# W108C.net
KiCad netlist of a schematic drawn in EAGLE
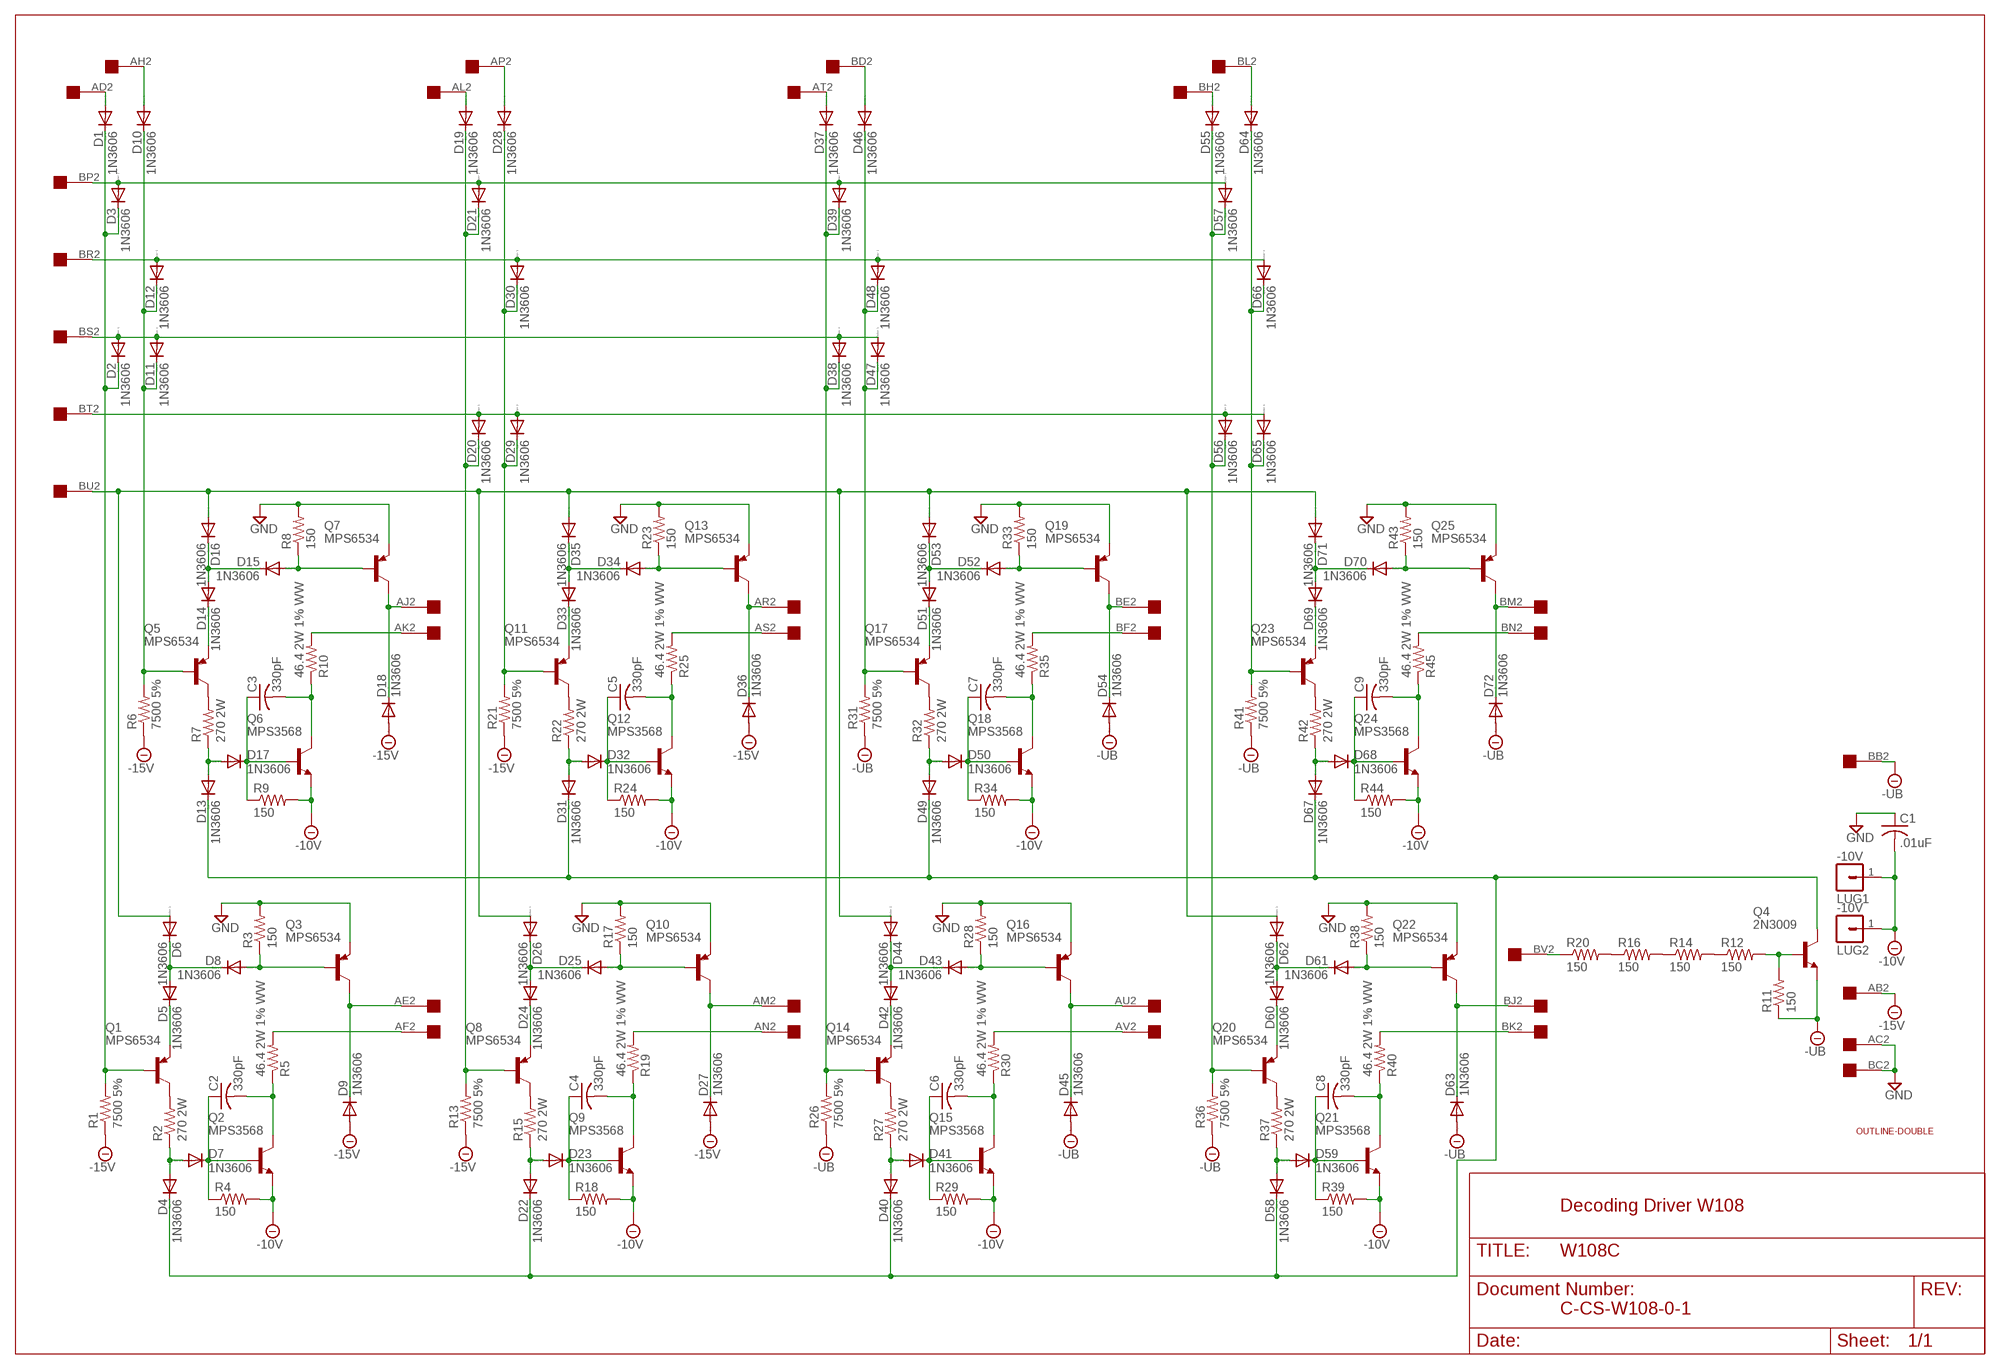
[diagram p0: schematic, sheet 1]

(export (version "E")
  (design (tool "Eeschema 10.0.6"))
  (components
    (comp (ref "C1")
      (value ".01uF")
      (footprint "eagle-import:C075-032X103")
      (libsource (lib "eagle-import") (part "C-US075-032X103"))
    )
    (comp (ref "C2")
      (value "330pF")
      (footprint "eagle-import:C075-032X103")
      (libsource (lib "eagle-import") (part "C-US075-032X103"))
    )
    (comp (ref "C3")
      (value "330pF")
      (footprint "eagle-import:C075-032X103")
      (libsource (lib "eagle-import") (part "C-US075-032X103"))
    )
    (comp (ref "C4")
      (value "330pF")
      (footprint "eagle-import:C075-032X103")
      (libsource (lib "eagle-import") (part "C-US075-032X103"))
    )
    (comp (ref "C5")
      (value "330pF")
      (footprint "eagle-import:C075-032X103")
      (libsource (lib "eagle-import") (part "C-US075-032X103"))
    )
    (comp (ref "C6")
      (value "330pF")
      (footprint "eagle-import:C075-032X103")
      (libsource (lib "eagle-import") (part "C-US075-032X103"))
    )
    (comp (ref "C7")
      (value "330pF")
      (footprint "eagle-import:C075-032X103")
      (libsource (lib "eagle-import") (part "C-US075-032X103"))
    )
    (comp (ref "C8")
      (value "330pF")
      (footprint "eagle-import:C075-032X103")
      (libsource (lib "eagle-import") (part "C-US075-032X103"))
    )
    (comp (ref "C9")
      (value "330pF")
      (footprint "eagle-import:C075-032X103")
      (libsource (lib "eagle-import") (part "C-US075-032X103"))
    )
    (comp (ref "D1")
      (value "1N3606")
      (footprint "eagle-import:DO35-10")
      (libsource (lib "eagle-import") (part "1N4148DO35-10"))
    )
    (comp (ref "D2")
      (value "1N3606")
      (footprint "eagle-import:DO35-10")
      (libsource (lib "eagle-import") (part "1N4148DO35-10"))
    )
    (comp (ref "D3")
      (value "1N3606")
      (footprint "eagle-import:DO35-10")
      (libsource (lib "eagle-import") (part "1N4148DO35-10"))
    )
    (comp (ref "D4")
      (value "1N3606")
      (footprint "eagle-import:DO35-10")
      (libsource (lib "eagle-import") (part "1N4148DO35-10"))
    )
    (comp (ref "D5")
      (value "1N3606")
      (footprint "eagle-import:DO35-10")
      (libsource (lib "eagle-import") (part "1N4148DO35-10"))
    )
    (comp (ref "D6")
      (value "1N3606")
      (footprint "eagle-import:DO35-10")
      (libsource (lib "eagle-import") (part "1N4148DO35-10"))
    )
    (comp (ref "D7")
      (value "1N3606")
      (footprint "eagle-import:DO35-10")
      (libsource (lib "eagle-import") (part "1N4148DO35-10"))
    )
    (comp (ref "D8")
      (value "1N3606")
      (footprint "eagle-import:DO35-10")
      (libsource (lib "eagle-import") (part "1N4148DO35-10"))
    )
    (comp (ref "D9")
      (value "1N3606")
      (footprint "eagle-import:DO35-10")
      (libsource (lib "eagle-import") (part "1N4148DO35-10"))
    )
    (comp (ref "D10")
      (value "1N3606")
      (footprint "eagle-import:DO35-10")
      (libsource (lib "eagle-import") (part "1N4148DO35-10"))
    )
    (comp (ref "D11")
      (value "1N3606")
      (footprint "eagle-import:DO35-10")
      (libsource (lib "eagle-import") (part "1N4148DO35-10"))
    )
    (comp (ref "D12")
      (value "1N3606")
      (footprint "eagle-import:DO35-10")
      (libsource (lib "eagle-import") (part "1N4148DO35-10"))
    )
    (comp (ref "D13")
      (value "1N3606")
      (footprint "eagle-import:DO35-10")
      (libsource (lib "eagle-import") (part "1N4148DO35-10"))
    )
    (comp (ref "D14")
      (value "1N3606")
      (footprint "eagle-import:DO35-10")
      (libsource (lib "eagle-import") (part "1N4148DO35-10"))
    )
    (comp (ref "D15")
      (value "1N3606")
      (footprint "eagle-import:DO35-10")
      (libsource (lib "eagle-import") (part "1N4148DO35-10"))
    )
    (comp (ref "D16")
      (value "1N3606")
      (footprint "eagle-import:DO35-10")
      (libsource (lib "eagle-import") (part "1N4148DO35-10"))
    )
    (comp (ref "D17")
      (value "1N3606")
      (footprint "eagle-import:DO35-10")
      (libsource (lib "eagle-import") (part "1N4148DO35-10"))
    )
    (comp (ref "D18")
      (value "1N3606")
      (footprint "eagle-import:DO35-10")
      (libsource (lib "eagle-import") (part "1N4148DO35-10"))
    )
    (comp (ref "D19")
      (value "1N3606")
      (footprint "eagle-import:DO35-10")
      (libsource (lib "eagle-import") (part "1N4148DO35-10"))
    )
    (comp (ref "D20")
      (value "1N3606")
      (footprint "eagle-import:DO35-10")
      (libsource (lib "eagle-import") (part "1N4148DO35-10"))
    )
    (comp (ref "D21")
      (value "1N3606")
      (footprint "eagle-import:DO35-10")
      (libsource (lib "eagle-import") (part "1N4148DO35-10"))
    )
    (comp (ref "D22")
      (value "1N3606")
      (footprint "eagle-import:DO35-10")
      (libsource (lib "eagle-import") (part "1N4148DO35-10"))
    )
    (comp (ref "D23")
      (value "1N3606")
      (footprint "eagle-import:DO35-10")
      (libsource (lib "eagle-import") (part "1N4148DO35-10"))
    )
    (comp (ref "D24")
      (value "1N3606")
      (footprint "eagle-import:DO35-10")
      (libsource (lib "eagle-import") (part "1N4148DO35-10"))
    )
    (comp (ref "D25")
      (value "1N3606")
      (footprint "eagle-import:DO35-10")
      (libsource (lib "eagle-import") (part "1N4148DO35-10"))
    )
    (comp (ref "D26")
      (value "1N3606")
      (footprint "eagle-import:DO35-10")
      (libsource (lib "eagle-import") (part "1N4148DO35-10"))
    )
    (comp (ref "D27")
      (value "1N3606")
      (footprint "eagle-import:DO35-10")
      (libsource (lib "eagle-import") (part "1N4148DO35-10"))
    )
    (comp (ref "D28")
      (value "1N3606")
      (footprint "eagle-import:DO35-10")
      (libsource (lib "eagle-import") (part "1N4148DO35-10"))
    )
    (comp (ref "D29")
      (value "1N3606")
      (footprint "eagle-import:DO35-10")
      (libsource (lib "eagle-import") (part "1N4148DO35-10"))
    )
    (comp (ref "D30")
      (value "1N3606")
      (footprint "eagle-import:DO35-10")
      (libsource (lib "eagle-import") (part "1N4148DO35-10"))
    )
    (comp (ref "D31")
      (value "1N3606")
      (footprint "eagle-import:DO35-10")
      (libsource (lib "eagle-import") (part "1N4148DO35-10"))
    )
    (comp (ref "D32")
      (value "1N3606")
      (footprint "eagle-import:DO35-10")
      (libsource (lib "eagle-import") (part "1N4148DO35-10"))
    )
    (comp (ref "D33")
      (value "1N3606")
      (footprint "eagle-import:DO35-10")
      (libsource (lib "eagle-import") (part "1N4148DO35-10"))
    )
    (comp (ref "D34")
      (value "1N3606")
      (footprint "eagle-import:DO35-10")
      (libsource (lib "eagle-import") (part "1N4148DO35-10"))
    )
    (comp (ref "D35")
      (value "1N3606")
      (footprint "eagle-import:DO35-10")
      (libsource (lib "eagle-import") (part "1N4148DO35-10"))
    )
    (comp (ref "D36")
      (value "1N3606")
      (footprint "eagle-import:DO35-10")
      (libsource (lib "eagle-import") (part "1N4148DO35-10"))
    )
    (comp (ref "D37")
      (value "1N3606")
      (footprint "eagle-import:DO35-10")
      (libsource (lib "eagle-import") (part "1N4148DO35-10"))
    )
    (comp (ref "D38")
      (value "1N3606")
      (footprint "eagle-import:DO35-10")
      (libsource (lib "eagle-import") (part "1N4148DO35-10"))
    )
    (comp (ref "D39")
      (value "1N3606")
      (footprint "eagle-import:DO35-10")
      (libsource (lib "eagle-import") (part "1N4148DO35-10"))
    )
    (comp (ref "D40")
      (value "1N3606")
      (footprint "eagle-import:DO35-10")
      (libsource (lib "eagle-import") (part "1N4148DO35-10"))
    )
    (comp (ref "D41")
      (value "1N3606")
      (footprint "eagle-import:DO35-10")
      (libsource (lib "eagle-import") (part "1N4148DO35-10"))
    )
    (comp (ref "D42")
      (value "1N3606")
      (footprint "eagle-import:DO35-10")
      (libsource (lib "eagle-import") (part "1N4148DO35-10"))
    )
    (comp (ref "D43")
      (value "1N3606")
      (footprint "eagle-import:DO35-10")
      (libsource (lib "eagle-import") (part "1N4148DO35-10"))
    )
    (comp (ref "D44")
      (value "1N3606")
      (footprint "eagle-import:DO35-10")
      (libsource (lib "eagle-import") (part "1N4148DO35-10"))
    )
    (comp (ref "D45")
      (value "1N3606")
      (footprint "eagle-import:DO35-10")
      (libsource (lib "eagle-import") (part "1N4148DO35-10"))
    )
    (comp (ref "D46")
      (value "1N3606")
      (footprint "eagle-import:DO35-10")
      (libsource (lib "eagle-import") (part "1N4148DO35-10"))
    )
    (comp (ref "D47")
      (value "1N3606")
      (footprint "eagle-import:DO35-10")
      (libsource (lib "eagle-import") (part "1N4148DO35-10"))
    )
    (comp (ref "D48")
      (value "1N3606")
      (footprint "eagle-import:DO35-10")
      (libsource (lib "eagle-import") (part "1N4148DO35-10"))
    )
    (comp (ref "D49")
      (value "1N3606")
      (footprint "eagle-import:DO35-10")
      (libsource (lib "eagle-import") (part "1N4148DO35-10"))
    )
    (comp (ref "D50")
      (value "1N3606")
      (footprint "eagle-import:DO35-10")
      (libsource (lib "eagle-import") (part "1N4148DO35-10"))
    )
    (comp (ref "D51")
      (value "1N3606")
      (footprint "eagle-import:DO35-10")
      (libsource (lib "eagle-import") (part "1N4148DO35-10"))
    )
    (comp (ref "D52")
      (value "1N3606")
      (footprint "eagle-import:DO35-10")
      (libsource (lib "eagle-import") (part "1N4148DO35-10"))
    )
    (comp (ref "D53")
      (value "1N3606")
      (footprint "eagle-import:DO35-10")
      (libsource (lib "eagle-import") (part "1N4148DO35-10"))
    )
    (comp (ref "D54")
      (value "1N3606")
      (footprint "eagle-import:DO35-10")
      (libsource (lib "eagle-import") (part "1N4148DO35-10"))
    )
    (comp (ref "D55")
      (value "1N3606")
      (footprint "eagle-import:DO35-10")
      (libsource (lib "eagle-import") (part "1N4148DO35-10"))
    )
    (comp (ref "D56")
      (value "1N3606")
      (footprint "eagle-import:DO35-10")
      (libsource (lib "eagle-import") (part "1N4148DO35-10"))
    )
    (comp (ref "D57")
      (value "1N3606")
      (footprint "eagle-import:DO35-10")
      (libsource (lib "eagle-import") (part "1N4148DO35-10"))
    )
    (comp (ref "D58")
      (value "1N3606")
      (footprint "eagle-import:DO35-10")
      (libsource (lib "eagle-import") (part "1N4148DO35-10"))
    )
    (comp (ref "D59")
      (value "1N3606")
      (footprint "eagle-import:DO35-10")
      (libsource (lib "eagle-import") (part "1N4148DO35-10"))
    )
    (comp (ref "D60")
      (value "1N3606")
      (footprint "eagle-import:DO35-10")
      (libsource (lib "eagle-import") (part "1N4148DO35-10"))
    )
    (comp (ref "D61")
      (value "1N3606")
      (footprint "eagle-import:DO35-10")
      (libsource (lib "eagle-import") (part "1N4148DO35-10"))
    )
    (comp (ref "D62")
      (value "1N3606")
      (footprint "eagle-import:DO35-10")
      (libsource (lib "eagle-import") (part "1N4148DO35-10"))
    )
    (comp (ref "D63")
      (value "1N3606")
      (footprint "eagle-import:DO35-10")
      (libsource (lib "eagle-import") (part "1N4148DO35-10"))
    )
    (comp (ref "D64")
      (value "1N3606")
      (footprint "eagle-import:DO35-10")
      (libsource (lib "eagle-import") (part "1N4148DO35-10"))
    )
    (comp (ref "D65")
      (value "1N3606")
      (footprint "eagle-import:DO35-10")
      (libsource (lib "eagle-import") (part "1N4148DO35-10"))
    )
    (comp (ref "D66")
      (value "1N3606")
      (footprint "eagle-import:DO35-10")
      (libsource (lib "eagle-import") (part "1N4148DO35-10"))
    )
    (comp (ref "D67")
      (value "1N3606")
      (footprint "eagle-import:DO35-10")
      (libsource (lib "eagle-import") (part "1N4148DO35-10"))
    )
    (comp (ref "D68")
      (value "1N3606")
      (footprint "eagle-import:DO35-10")
      (libsource (lib "eagle-import") (part "1N4148DO35-10"))
    )
    (comp (ref "D69")
      (value "1N3606")
      (footprint "eagle-import:DO35-10")
      (libsource (lib "eagle-import") (part "1N4148DO35-10"))
    )
    (comp (ref "D70")
      (value "1N3606")
      (footprint "eagle-import:DO35-10")
      (libsource (lib "eagle-import") (part "1N4148DO35-10"))
    )
    (comp (ref "D71")
      (value "1N3606")
      (footprint "eagle-import:DO35-10")
      (libsource (lib "eagle-import") (part "1N4148DO35-10"))
    )
    (comp (ref "D72")
      (value "1N3606")
      (footprint "eagle-import:DO35-10")
      (libsource (lib "eagle-import") (part "1N4148DO35-10"))
    )
    (comp (ref "LUG1")
      (value "-10V")
      (footprint "eagle-import:SPADELUG")
      (libsource (lib "eagle-import") (part "LUG"))
    )
    (comp (ref "LUG2")
      (value "-10V")
      (footprint "eagle-import:SPADELUG")
      (libsource (lib "eagle-import") (part "LUG"))
    )
    (comp (ref "Q1")
      (value "MPS6534")
      (footprint "eagle-import:TO39")
      (libsource (lib "eagle-import") (part "2N2904"))
    )
    (comp (ref "Q2")
      (value "MPS3568")
      (footprint "eagle-import:TO5")
      (libsource (lib "eagle-import") (part "2N2102"))
    )
    (comp (ref "Q3")
      (value "MPS6534")
      (footprint "eagle-import:TO39")
      (libsource (lib "eagle-import") (part "2N2904"))
    )
    (comp (ref "Q4")
      (value "2N3009")
      (footprint "eagle-import:TO5")
      (libsource (lib "eagle-import") (part "2N2102"))
    )
    (comp (ref "Q5")
      (value "MPS6534")
      (footprint "eagle-import:TO39")
      (libsource (lib "eagle-import") (part "2N2904"))
    )
    (comp (ref "Q6")
      (value "MPS3568")
      (footprint "eagle-import:TO5")
      (libsource (lib "eagle-import") (part "2N2102"))
    )
    (comp (ref "Q7")
      (value "MPS6534")
      (footprint "eagle-import:TO39")
      (libsource (lib "eagle-import") (part "2N2904"))
    )
    (comp (ref "Q8")
      (value "MPS6534")
      (footprint "eagle-import:TO39")
      (libsource (lib "eagle-import") (part "2N2904"))
    )
    (comp (ref "Q9")
      (value "MPS3568")
      (footprint "eagle-import:TO5")
      (libsource (lib "eagle-import") (part "2N2102"))
    )
    (comp (ref "Q10")
      (value "MPS6534")
      (footprint "eagle-import:TO39")
      (libsource (lib "eagle-import") (part "2N2904"))
    )
    (comp (ref "Q11")
      (value "MPS6534")
      (footprint "eagle-import:TO39")
      (libsource (lib "eagle-import") (part "2N2904"))
    )
    (comp (ref "Q12")
      (value "MPS3568")
      (footprint "eagle-import:TO5")
      (libsource (lib "eagle-import") (part "2N2102"))
    )
    (comp (ref "Q13")
      (value "MPS6534")
      (footprint "eagle-import:TO39")
      (libsource (lib "eagle-import") (part "2N2904"))
    )
    (comp (ref "Q14")
      (value "MPS6534")
      (footprint "eagle-import:TO39")
      (libsource (lib "eagle-import") (part "2N2904"))
    )
    (comp (ref "Q15")
      (value "MPS3568")
      (footprint "eagle-import:TO5")
      (libsource (lib "eagle-import") (part "2N2102"))
    )
    (comp (ref "Q16")
      (value "MPS6534")
      (footprint "eagle-import:TO39")
      (libsource (lib "eagle-import") (part "2N2904"))
    )
    (comp (ref "Q17")
      (value "MPS6534")
      (footprint "eagle-import:TO39")
      (libsource (lib "eagle-import") (part "2N2904"))
    )
    (comp (ref "Q18")
      (value "MPS3568")
      (footprint "eagle-import:TO5")
      (libsource (lib "eagle-import") (part "2N2102"))
    )
    (comp (ref "Q19")
      (value "MPS6534")
      (footprint "eagle-import:TO39")
      (libsource (lib "eagle-import") (part "2N2904"))
    )
    (comp (ref "Q20")
      (value "MPS6534")
      (footprint "eagle-import:TO39")
      (libsource (lib "eagle-import") (part "2N2904"))
    )
    (comp (ref "Q21")
      (value "MPS3568")
      (footprint "eagle-import:TO5")
      (libsource (lib "eagle-import") (part "2N2102"))
    )
    (comp (ref "Q22")
      (value "MPS6534")
      (footprint "eagle-import:TO39")
      (libsource (lib "eagle-import") (part "2N2904"))
    )
    (comp (ref "Q23")
      (value "MPS6534")
      (footprint "eagle-import:TO39")
      (libsource (lib "eagle-import") (part "2N2904"))
    )
    (comp (ref "Q24")
      (value "MPS3568")
      (footprint "eagle-import:TO5")
      (libsource (lib "eagle-import") (part "2N2102"))
    )
    (comp (ref "Q25")
      (value "MPS6534")
      (footprint "eagle-import:TO39")
      (libsource (lib "eagle-import") (part "2N2904"))
    )
    (comp (ref "R1")
      (value "7500 5%")
      (footprint "eagle-import:0207_10")
      (libsource (lib "eagle-import") (part "R-US_0207/10"))
    )
    (comp (ref "R2")
      (value "270 2W")
      (footprint "eagle-import:0617_22")
      (libsource (lib "eagle-import") (part "R-US_0617/22"))
    )
    (comp (ref "R3")
      (value "150")
      (footprint "eagle-import:0207_10")
      (libsource (lib "eagle-import") (part "R-US_0207/10"))
    )
    (comp (ref "R4")
      (value "150")
      (footprint "eagle-import:0207_10")
      (libsource (lib "eagle-import") (part "R-US_0207/10"))
    )
    (comp (ref "R5")
      (value "46.4 2W 1% WW")
      (footprint "eagle-import:0414_20")
      (libsource (lib "eagle-import") (part "R-US_0414/20"))
    )
    (comp (ref "R6")
      (value "7500 5%")
      (footprint "eagle-import:0207_10")
      (libsource (lib "eagle-import") (part "R-US_0207/10"))
    )
    (comp (ref "R7")
      (value "270 2W")
      (footprint "eagle-import:0617_22")
      (libsource (lib "eagle-import") (part "R-US_0617/22"))
    )
    (comp (ref "R8")
      (value "150")
      (footprint "eagle-import:0207_10")
      (libsource (lib "eagle-import") (part "R-US_0207/10"))
    )
    (comp (ref "R9")
      (value "150")
      (footprint "eagle-import:0207_10")
      (libsource (lib "eagle-import") (part "R-US_0207/10"))
    )
    (comp (ref "R10")
      (value "46.4 2W 1% WW")
      (footprint "eagle-import:0414_20")
      (libsource (lib "eagle-import") (part "R-US_0414/20"))
    )
    (comp (ref "R11")
      (value "150")
      (footprint "eagle-import:0207_10")
      (libsource (lib "eagle-import") (part "R-US_0207/10"))
    )
    (comp (ref "R12")
      (value "150")
      (footprint "eagle-import:0207_10")
      (libsource (lib "eagle-import") (part "R-US_0207/10"))
    )
    (comp (ref "R13")
      (value "7500 5%")
      (footprint "eagle-import:0207_10")
      (libsource (lib "eagle-import") (part "R-US_0207/10"))
    )
    (comp (ref "R14")
      (value "150")
      (footprint "eagle-import:0207_10")
      (libsource (lib "eagle-import") (part "R-US_0207/10"))
    )
    (comp (ref "R15")
      (value "270 2W")
      (footprint "eagle-import:0617_22")
      (libsource (lib "eagle-import") (part "R-US_0617/22"))
    )
    (comp (ref "R16")
      (value "150")
      (footprint "eagle-import:0207_10")
      (libsource (lib "eagle-import") (part "R-US_0207/10"))
    )
    (comp (ref "R17")
      (value "150")
      (footprint "eagle-import:0207_10")
      (libsource (lib "eagle-import") (part "R-US_0207/10"))
    )
    (comp (ref "R18")
      (value "150")
      (footprint "eagle-import:0207_10")
      (libsource (lib "eagle-import") (part "R-US_0207/10"))
    )
    (comp (ref "R19")
      (value "46.4 2W 1% WW")
      (footprint "eagle-import:0414_20")
      (libsource (lib "eagle-import") (part "R-US_0414/20"))
    )
    (comp (ref "R20")
      (value "150")
      (footprint "eagle-import:0207_10")
      (libsource (lib "eagle-import") (part "R-US_0207/10"))
    )
    (comp (ref "R21")
      (value "7500 5%")
      (footprint "eagle-import:0207_10")
      (libsource (lib "eagle-import") (part "R-US_0207/10"))
    )
    (comp (ref "R22")
      (value "270 2W")
      (footprint "eagle-import:0617_22")
      (libsource (lib "eagle-import") (part "R-US_0617/22"))
    )
    (comp (ref "R23")
      (value "150")
      (footprint "eagle-import:0207_10")
      (libsource (lib "eagle-import") (part "R-US_0207/10"))
    )
    (comp (ref "R24")
      (value "150")
      (footprint "eagle-import:0207_10")
      (libsource (lib "eagle-import") (part "R-US_0207/10"))
    )
    (comp (ref "R25")
      (value "46.4 2W 1% WW")
      (footprint "eagle-import:0414_20")
      (libsource (lib "eagle-import") (part "R-US_0414/20"))
    )
    (comp (ref "R26")
      (value "7500 5%")
      (footprint "eagle-import:0207_10")
      (libsource (lib "eagle-import") (part "R-US_0207/10"))
    )
    (comp (ref "R27")
      (value "270 2W")
      (footprint "eagle-import:0617_22")
      (libsource (lib "eagle-import") (part "R-US_0617/22"))
    )
    (comp (ref "R28")
      (value "150")
      (footprint "eagle-import:0207_10")
      (libsource (lib "eagle-import") (part "R-US_0207/10"))
    )
    (comp (ref "R29")
      (value "150")
      (footprint "eagle-import:0207_10")
      (libsource (lib "eagle-import") (part "R-US_0207/10"))
    )
    (comp (ref "R30")
      (value "46.4 2W 1% WW")
      (footprint "eagle-import:0414_20")
      (libsource (lib "eagle-import") (part "R-US_0414/20"))
    )
    (comp (ref "R31")
      (value "7500 5%")
      (footprint "eagle-import:0207_10")
      (libsource (lib "eagle-import") (part "R-US_0207/10"))
    )
    (comp (ref "R32")
      (value "270 2W")
      (footprint "eagle-import:0617_22")
      (libsource (lib "eagle-import") (part "R-US_0617/22"))
    )
    (comp (ref "R33")
      (value "150")
      (footprint "eagle-import:0207_10")
      (libsource (lib "eagle-import") (part "R-US_0207/10"))
    )
    (comp (ref "R34")
      (value "150")
      (footprint "eagle-import:0207_10")
      (libsource (lib "eagle-import") (part "R-US_0207/10"))
    )
    (comp (ref "R35")
      (value "46.4 2W 1% WW")
      (footprint "eagle-import:0414_20")
      (libsource (lib "eagle-import") (part "R-US_0414/20"))
    )
    (comp (ref "R36")
      (value "7500 5%")
      (footprint "eagle-import:0207_10")
      (libsource (lib "eagle-import") (part "R-US_0207/10"))
    )
    (comp (ref "R37")
      (value "270 2W")
      (footprint "eagle-import:0617_22")
      (libsource (lib "eagle-import") (part "R-US_0617/22"))
    )
    (comp (ref "R38")
      (value "150")
      (footprint "eagle-import:0207_10")
      (libsource (lib "eagle-import") (part "R-US_0207/10"))
    )
    (comp (ref "R39")
      (value "150")
      (footprint "eagle-import:0207_10")
      (libsource (lib "eagle-import") (part "R-US_0207/10"))
    )
    (comp (ref "R40")
      (value "46.4 2W 1% WW")
      (footprint "eagle-import:0414_20")
      (libsource (lib "eagle-import") (part "R-US_0414/20"))
    )
    (comp (ref "R41")
      (value "7500 5%")
      (footprint "eagle-import:0207_10")
      (libsource (lib "eagle-import") (part "R-US_0207/10"))
    )
    (comp (ref "R42")
      (value "270 2W")
      (footprint "eagle-import:0617_22")
      (libsource (lib "eagle-import") (part "R-US_0617/22"))
    )
    (comp (ref "R43")
      (value "150")
      (footprint "eagle-import:0207_10")
      (libsource (lib "eagle-import") (part "R-US_0207/10"))
    )
    (comp (ref "R44")
      (value "150")
      (footprint "eagle-import:0207_10")
      (libsource (lib "eagle-import") (part "R-US_0207/10"))
    )
    (comp (ref "R45")
      (value "46.4 2W 1% WW")
      (footprint "eagle-import:0414_20")
      (libsource (lib "eagle-import") (part "R-US_0414/20"))
    )
    (comp (ref "U$1")
      (value "OUTLINE-DOUBLE")
      (footprint "eagle-import:DOUBLE")
      (libsource (lib "eagle-import") (part "OUTLINE-DOUBLE"))
    )
    (comp (ref "U$2")
      (value "DOUBLE")
      (footprint "eagle-import:EDGE-CON4")
      (libsource (lib "eagle-import") (part "DOUBLE"))
    )
  )
  (nets
    (net (code "1") (name "-10V") (class "Default")
      (node (ref "C1") (pin "2") (pinfunction "2_2") (pintype "passive"))
      (node (ref "LUG1") (pin "1") (pinfunction "1_1") (pintype "passive"))
      (node (ref "LUG2") (pin "1") (pinfunction "1_1") (pintype "passive"))
      (node (ref "Q12") (pin "1") (pinfunction "E_1") (pintype "passive"))
      (node (ref "Q15") (pin "1") (pinfunction "E_1") (pintype "passive"))
      (node (ref "Q18") (pin "1") (pinfunction "E_1") (pintype "passive"))
      (node (ref "Q2") (pin "1") (pinfunction "E_1") (pintype "passive"))
      (node (ref "Q21") (pin "1") (pinfunction "E_1") (pintype "passive"))
      (node (ref "Q24") (pin "1") (pinfunction "E_1") (pintype "passive"))
      (node (ref "Q6") (pin "1") (pinfunction "E_1") (pintype "passive"))
      (node (ref "Q9") (pin "1") (pinfunction "E_1") (pintype "passive"))
      (node (ref "R18") (pin "2") (pinfunction "2_2") (pintype "passive"))
      (node (ref "R24") (pin "2") (pinfunction "2_2") (pintype "passive"))
      (node (ref "R29") (pin "2") (pinfunction "2_2") (pintype "passive"))
      (node (ref "R34") (pin "2") (pinfunction "2_2") (pintype "passive"))
      (node (ref "R39") (pin "2") (pinfunction "2_2") (pintype "passive"))
      (node (ref "R4") (pin "2") (pinfunction "2_2") (pintype "passive"))
      (node (ref "R44") (pin "2") (pinfunction "2_2") (pintype "passive"))
      (node (ref "R9") (pin "2") (pinfunction "2_2") (pintype "passive"))
    )
    (net (code "2") (name "-15V") (class "Default")
      (node (ref "D18") (pin "A") (pinfunction "A_A") (pintype "passive"))
      (node (ref "D27") (pin "A") (pinfunction "A_A") (pintype "passive"))
      (node (ref "D36") (pin "A") (pinfunction "A_A") (pintype "passive"))
      (node (ref "D9") (pin "A") (pinfunction "A_A") (pintype "passive"))
      (node (ref "R1") (pin "1") (pinfunction "1_1") (pintype "passive"))
      (node (ref "R13") (pin "1") (pinfunction "1_1") (pintype "passive"))
      (node (ref "R21") (pin "1") (pinfunction "1_1") (pintype "passive"))
      (node (ref "R6") (pin "1") (pinfunction "1_1") (pintype "passive"))
      (node (ref "U$2") (pin "AB2") (pinfunction "1_AB2") (pintype "bidirectional"))
    )
    (net (code "3") (name "-UB") (class "Default")
      (node (ref "D45") (pin "A") (pinfunction "A_A") (pintype "passive"))
      (node (ref "D54") (pin "A") (pinfunction "A_A") (pintype "passive"))
      (node (ref "D63") (pin "A") (pinfunction "A_A") (pintype "passive"))
      (node (ref "D72") (pin "A") (pinfunction "A_A") (pintype "passive"))
      (node (ref "Q4") (pin "1") (pinfunction "E_1") (pintype "passive"))
      (node (ref "R11") (pin "1") (pinfunction "1_1") (pintype "passive"))
      (node (ref "R26") (pin "1") (pinfunction "1_1") (pintype "passive"))
      (node (ref "R31") (pin "1") (pinfunction "1_1") (pintype "passive"))
      (node (ref "R36") (pin "1") (pinfunction "1_1") (pintype "passive"))
      (node (ref "R41") (pin "1") (pinfunction "1_1") (pintype "passive"))
      (node (ref "U$2") (pin "BB2") (pinfunction "1_BB2") (pintype "bidirectional"))
    )
    (net (code "4") (name "GND") (class "Default")
      (node (ref "C1") (pin "1") (pinfunction "1_1") (pintype "passive"))
      (node (ref "Q10") (pin "1") (pinfunction "E_1") (pintype "passive"))
      (node (ref "Q13") (pin "1") (pinfunction "E_1") (pintype "passive"))
      (node (ref "Q16") (pin "1") (pinfunction "E_1") (pintype "passive"))
      (node (ref "Q19") (pin "1") (pinfunction "E_1") (pintype "passive"))
      (node (ref "Q22") (pin "1") (pinfunction "E_1") (pintype "passive"))
      (node (ref "Q25") (pin "1") (pinfunction "E_1") (pintype "passive"))
      (node (ref "Q3") (pin "1") (pinfunction "E_1") (pintype "passive"))
      (node (ref "Q7") (pin "1") (pinfunction "E_1") (pintype "passive"))
      (node (ref "R17") (pin "2") (pinfunction "2_2") (pintype "passive"))
      (node (ref "R23") (pin "2") (pinfunction "2_2") (pintype "passive"))
      (node (ref "R28") (pin "2") (pinfunction "2_2") (pintype "passive"))
      (node (ref "R3") (pin "2") (pinfunction "2_2") (pintype "passive"))
      (node (ref "R33") (pin "2") (pinfunction "2_2") (pintype "passive"))
      (node (ref "R38") (pin "2") (pinfunction "2_2") (pintype "passive"))
      (node (ref "R43") (pin "2") (pinfunction "2_2") (pintype "passive"))
      (node (ref "R8") (pin "2") (pinfunction "2_2") (pintype "passive"))
      (node (ref "U$2") (pin "AC2") (pinfunction "1_AC2") (pintype "bidirectional"))
      (node (ref "U$2") (pin "BC2") (pinfunction "1_BC2") (pintype "bidirectional"))
    )
    (net (code "5") (name "Net-(D4-PadA)") (class "Default")
      (node (ref "D4") (pin "A") (pinfunction "A_A") (pintype "passive"))
      (node (ref "D7") (pin "A") (pinfunction "A_A") (pintype "passive"))
      (node (ref "R2") (pin "1") (pinfunction "1_1") (pintype "passive"))
    )
    (net (code "6") (name "Net-(D5-PadA)") (class "Default")
      (node (ref "D5") (pin "A") (pinfunction "A_A") (pintype "passive"))
      (node (ref "D6") (pin "C") (pinfunction "C_C") (pintype "passive"))
      (node (ref "D8") (pin "C") (pinfunction "C_C") (pintype "passive"))
    )
    (net (code "7") (name "Net-(D13-PadA)") (class "Default")
      (node (ref "D13") (pin "A") (pinfunction "A_A") (pintype "passive"))
      (node (ref "D17") (pin "A") (pinfunction "A_A") (pintype "passive"))
      (node (ref "R7") (pin "1") (pinfunction "1_1") (pintype "passive"))
    )
    (net (code "8") (name "Net-(D14-PadA)") (class "Default")
      (node (ref "D14") (pin "A") (pinfunction "A_A") (pintype "passive"))
      (node (ref "D15") (pin "C") (pinfunction "C_C") (pintype "passive"))
      (node (ref "D16") (pin "C") (pinfunction "C_C") (pintype "passive"))
    )
    (net (code "9") (name "Net-(D22-PadA)") (class "Default")
      (node (ref "D22") (pin "A") (pinfunction "A_A") (pintype "passive"))
      (node (ref "D23") (pin "A") (pinfunction "A_A") (pintype "passive"))
      (node (ref "R15") (pin "1") (pinfunction "1_1") (pintype "passive"))
    )
    (net (code "10") (name "Net-(D24-PadA)") (class "Default")
      (node (ref "D24") (pin "A") (pinfunction "A_A") (pintype "passive"))
      (node (ref "D25") (pin "C") (pinfunction "C_C") (pintype "passive"))
      (node (ref "D26") (pin "C") (pinfunction "C_C") (pintype "passive"))
    )
    (net (code "11") (name "Net-(D31-PadA)") (class "Default")
      (node (ref "D31") (pin "A") (pinfunction "A_A") (pintype "passive"))
      (node (ref "D32") (pin "A") (pinfunction "A_A") (pintype "passive"))
      (node (ref "R22") (pin "1") (pinfunction "1_1") (pintype "passive"))
    )
    (net (code "12") (name "Net-(D33-PadA)") (class "Default")
      (node (ref "D33") (pin "A") (pinfunction "A_A") (pintype "passive"))
      (node (ref "D34") (pin "C") (pinfunction "C_C") (pintype "passive"))
      (node (ref "D35") (pin "C") (pinfunction "C_C") (pintype "passive"))
    )
    (net (code "13") (name "Net-(D40-PadA)") (class "Default")
      (node (ref "D40") (pin "A") (pinfunction "A_A") (pintype "passive"))
      (node (ref "D41") (pin "A") (pinfunction "A_A") (pintype "passive"))
      (node (ref "R27") (pin "1") (pinfunction "1_1") (pintype "passive"))
    )
    (net (code "14") (name "Net-(D42-PadA)") (class "Default")
      (node (ref "D42") (pin "A") (pinfunction "A_A") (pintype "passive"))
      (node (ref "D43") (pin "C") (pinfunction "C_C") (pintype "passive"))
      (node (ref "D44") (pin "C") (pinfunction "C_C") (pintype "passive"))
    )
    (net (code "15") (name "Net-(D49-PadA)") (class "Default")
      (node (ref "D49") (pin "A") (pinfunction "A_A") (pintype "passive"))
      (node (ref "D50") (pin "A") (pinfunction "A_A") (pintype "passive"))
      (node (ref "R32") (pin "1") (pinfunction "1_1") (pintype "passive"))
    )
    (net (code "16") (name "Net-(D51-PadA)") (class "Default")
      (node (ref "D51") (pin "A") (pinfunction "A_A") (pintype "passive"))
      (node (ref "D52") (pin "C") (pinfunction "C_C") (pintype "passive"))
      (node (ref "D53") (pin "C") (pinfunction "C_C") (pintype "passive"))
    )
    (net (code "17") (name "Net-(D58-PadA)") (class "Default")
      (node (ref "D58") (pin "A") (pinfunction "A_A") (pintype "passive"))
      (node (ref "D59") (pin "A") (pinfunction "A_A") (pintype "passive"))
      (node (ref "R37") (pin "1") (pinfunction "1_1") (pintype "passive"))
    )
    (net (code "18") (name "Net-(D60-PadA)") (class "Default")
      (node (ref "D60") (pin "A") (pinfunction "A_A") (pintype "passive"))
      (node (ref "D61") (pin "C") (pinfunction "C_C") (pintype "passive"))
      (node (ref "D62") (pin "C") (pinfunction "C_C") (pintype "passive"))
    )
    (net (code "19") (name "Net-(D67-PadA)") (class "Default")
      (node (ref "D67") (pin "A") (pinfunction "A_A") (pintype "passive"))
      (node (ref "D68") (pin "A") (pinfunction "A_A") (pintype "passive"))
      (node (ref "R42") (pin "1") (pinfunction "1_1") (pintype "passive"))
    )
    (net (code "20") (name "Net-(D69-PadA)") (class "Default")
      (node (ref "D69") (pin "A") (pinfunction "A_A") (pintype "passive"))
      (node (ref "D70") (pin "C") (pinfunction "C_C") (pintype "passive"))
      (node (ref "D71") (pin "C") (pinfunction "C_C") (pintype "passive"))
    )
    (net (code "21") (name "Net-(Q1-B)") (class "Default")
      (node (ref "D1") (pin "C") (pinfunction "C_C") (pintype "passive"))
      (node (ref "D2") (pin "C") (pinfunction "C_C") (pintype "passive"))
      (node (ref "D3") (pin "C") (pinfunction "C_C") (pintype "passive"))
      (node (ref "Q1") (pin "2") (pinfunction "B_2") (pintype "passive"))
      (node (ref "R1") (pin "2") (pinfunction "2_2") (pintype "passive"))
    )
    (net (code "22") (name "Net-(Q1-C)") (class "Default")
      (node (ref "Q1") (pin "3") (pinfunction "C_3") (pintype "passive"))
      (node (ref "R2") (pin "2") (pinfunction "2_2") (pintype "passive"))
    )
    (net (code "23") (name "Net-(Q1-E)") (class "Default")
      (node (ref "D5") (pin "C") (pinfunction "C_C") (pintype "passive"))
      (node (ref "Q1") (pin "1") (pinfunction "E_1") (pintype "passive"))
    )
    (net (code "24") (name "Net-(Q2-B)") (class "Default")
      (node (ref "C2") (pin "1") (pinfunction "1_1") (pintype "passive"))
      (node (ref "D7") (pin "C") (pinfunction "C_C") (pintype "passive"))
      (node (ref "Q2") (pin "2") (pinfunction "B_2") (pintype "passive"))
      (node (ref "R4") (pin "1") (pinfunction "1_1") (pintype "passive"))
    )
    (net (code "25") (name "Net-(Q2-C)") (class "Default")
      (node (ref "C2") (pin "2") (pinfunction "2_2") (pintype "passive"))
      (node (ref "Q2") (pin "3") (pinfunction "C_3") (pintype "passive"))
      (node (ref "R5") (pin "1") (pinfunction "1_1") (pintype "passive"))
    )
    (net (code "26") (name "Net-(Q3-B)") (class "Default")
      (node (ref "D8") (pin "A") (pinfunction "A_A") (pintype "passive"))
      (node (ref "Q3") (pin "2") (pinfunction "B_2") (pintype "passive"))
      (node (ref "R3") (pin "1") (pinfunction "1_1") (pintype "passive"))
    )
    (net (code "27") (name "Net-(Q3-C)") (class "Default")
      (node (ref "D9") (pin "C") (pinfunction "C_C") (pintype "passive"))
      (node (ref "Q3") (pin "3") (pinfunction "C_3") (pintype "passive"))
      (node (ref "U$2") (pin "AE2") (pinfunction "1_AE2") (pintype "bidirectional"))
    )
    (net (code "28") (name "Net-(Q4-B)") (class "Default")
      (node (ref "Q4") (pin "2") (pinfunction "B_2") (pintype "passive"))
      (node (ref "R11") (pin "2") (pinfunction "2_2") (pintype "passive"))
      (node (ref "R12") (pin "2") (pinfunction "2_2") (pintype "passive"))
    )
    (net (code "29") (name "Net-(Q4-C)") (class "Default")
      (node (ref "D13") (pin "C") (pinfunction "C_C") (pintype "passive"))
      (node (ref "D22") (pin "C") (pinfunction "C_C") (pintype "passive"))
      (node (ref "D31") (pin "C") (pinfunction "C_C") (pintype "passive"))
      (node (ref "D4") (pin "C") (pinfunction "C_C") (pintype "passive"))
      (node (ref "D40") (pin "C") (pinfunction "C_C") (pintype "passive"))
      (node (ref "D49") (pin "C") (pinfunction "C_C") (pintype "passive"))
      (node (ref "D58") (pin "C") (pinfunction "C_C") (pintype "passive"))
      (node (ref "D67") (pin "C") (pinfunction "C_C") (pintype "passive"))
      (node (ref "Q4") (pin "3") (pinfunction "C_3") (pintype "passive"))
    )
    (net (code "30") (name "Net-(Q5-B)") (class "Default")
      (node (ref "D10") (pin "C") (pinfunction "C_C") (pintype "passive"))
      (node (ref "D11") (pin "C") (pinfunction "C_C") (pintype "passive"))
      (node (ref "D12") (pin "C") (pinfunction "C_C") (pintype "passive"))
      (node (ref "Q5") (pin "2") (pinfunction "B_2") (pintype "passive"))
      (node (ref "R6") (pin "2") (pinfunction "2_2") (pintype "passive"))
    )
    (net (code "31") (name "Net-(Q5-C)") (class "Default")
      (node (ref "Q5") (pin "3") (pinfunction "C_3") (pintype "passive"))
      (node (ref "R7") (pin "2") (pinfunction "2_2") (pintype "passive"))
    )
    (net (code "32") (name "Net-(Q5-E)") (class "Default")
      (node (ref "D14") (pin "C") (pinfunction "C_C") (pintype "passive"))
      (node (ref "Q5") (pin "1") (pinfunction "E_1") (pintype "passive"))
    )
    (net (code "33") (name "Net-(Q6-B)") (class "Default")
      (node (ref "C3") (pin "1") (pinfunction "1_1") (pintype "passive"))
      (node (ref "D17") (pin "C") (pinfunction "C_C") (pintype "passive"))
      (node (ref "Q6") (pin "2") (pinfunction "B_2") (pintype "passive"))
      (node (ref "R9") (pin "1") (pinfunction "1_1") (pintype "passive"))
    )
    (net (code "34") (name "Net-(Q6-C)") (class "Default")
      (node (ref "C3") (pin "2") (pinfunction "2_2") (pintype "passive"))
      (node (ref "Q6") (pin "3") (pinfunction "C_3") (pintype "passive"))
      (node (ref "R10") (pin "1") (pinfunction "1_1") (pintype "passive"))
    )
    (net (code "35") (name "Net-(Q7-B)") (class "Default")
      (node (ref "D15") (pin "A") (pinfunction "A_A") (pintype "passive"))
      (node (ref "Q7") (pin "2") (pinfunction "B_2") (pintype "passive"))
      (node (ref "R8") (pin "1") (pinfunction "1_1") (pintype "passive"))
    )
    (net (code "36") (name "Net-(Q7-C)") (class "Default")
      (node (ref "D18") (pin "C") (pinfunction "C_C") (pintype "passive"))
      (node (ref "Q7") (pin "3") (pinfunction "C_3") (pintype "passive"))
      (node (ref "U$2") (pin "AJ2") (pinfunction "1_AJ2") (pintype "bidirectional"))
    )
    (net (code "37") (name "Net-(Q8-B)") (class "Default")
      (node (ref "D19") (pin "C") (pinfunction "C_C") (pintype "passive"))
      (node (ref "D20") (pin "C") (pinfunction "C_C") (pintype "passive"))
      (node (ref "D21") (pin "C") (pinfunction "C_C") (pintype "passive"))
      (node (ref "Q8") (pin "2") (pinfunction "B_2") (pintype "passive"))
      (node (ref "R13") (pin "2") (pinfunction "2_2") (pintype "passive"))
    )
    (net (code "38") (name "Net-(Q8-C)") (class "Default")
      (node (ref "Q8") (pin "3") (pinfunction "C_3") (pintype "passive"))
      (node (ref "R15") (pin "2") (pinfunction "2_2") (pintype "passive"))
    )
    (net (code "39") (name "Net-(Q8-E)") (class "Default")
      (node (ref "D24") (pin "C") (pinfunction "C_C") (pintype "passive"))
      (node (ref "Q8") (pin "1") (pinfunction "E_1") (pintype "passive"))
    )
    (net (code "40") (name "Net-(Q9-B)") (class "Default")
      (node (ref "C4") (pin "1") (pinfunction "1_1") (pintype "passive"))
      (node (ref "D23") (pin "C") (pinfunction "C_C") (pintype "passive"))
      (node (ref "Q9") (pin "2") (pinfunction "B_2") (pintype "passive"))
      (node (ref "R18") (pin "1") (pinfunction "1_1") (pintype "passive"))
    )
    (net (code "41") (name "Net-(Q9-C)") (class "Default")
      (node (ref "C4") (pin "2") (pinfunction "2_2") (pintype "passive"))
      (node (ref "Q9") (pin "3") (pinfunction "C_3") (pintype "passive"))
      (node (ref "R19") (pin "1") (pinfunction "1_1") (pintype "passive"))
    )
    (net (code "42") (name "Net-(Q10-B)") (class "Default")
      (node (ref "D25") (pin "A") (pinfunction "A_A") (pintype "passive"))
      (node (ref "Q10") (pin "2") (pinfunction "B_2") (pintype "passive"))
      (node (ref "R17") (pin "1") (pinfunction "1_1") (pintype "passive"))
    )
    (net (code "43") (name "Net-(Q10-C)") (class "Default")
      (node (ref "D27") (pin "C") (pinfunction "C_C") (pintype "passive"))
      (node (ref "Q10") (pin "3") (pinfunction "C_3") (pintype "passive"))
      (node (ref "U$2") (pin "AM2") (pinfunction "1_AM2") (pintype "bidirectional"))
    )
    (net (code "44") (name "Net-(Q11-B)") (class "Default")
      (node (ref "D28") (pin "C") (pinfunction "C_C") (pintype "passive"))
      (node (ref "D29") (pin "C") (pinfunction "C_C") (pintype "passive"))
      (node (ref "D30") (pin "C") (pinfunction "C_C") (pintype "passive"))
      (node (ref "Q11") (pin "2") (pinfunction "B_2") (pintype "passive"))
      (node (ref "R21") (pin "2") (pinfunction "2_2") (pintype "passive"))
    )
    (net (code "45") (name "Net-(Q11-C)") (class "Default")
      (node (ref "Q11") (pin "3") (pinfunction "C_3") (pintype "passive"))
      (node (ref "R22") (pin "2") (pinfunction "2_2") (pintype "passive"))
    )
    (net (code "46") (name "Net-(Q11-E)") (class "Default")
      (node (ref "D33") (pin "C") (pinfunction "C_C") (pintype "passive"))
      (node (ref "Q11") (pin "1") (pinfunction "E_1") (pintype "passive"))
    )
    (net (code "47") (name "Net-(Q12-B)") (class "Default")
      (node (ref "C5") (pin "1") (pinfunction "1_1") (pintype "passive"))
      (node (ref "D32") (pin "C") (pinfunction "C_C") (pintype "passive"))
      (node (ref "Q12") (pin "2") (pinfunction "B_2") (pintype "passive"))
      (node (ref "R24") (pin "1") (pinfunction "1_1") (pintype "passive"))
    )
    (net (code "48") (name "Net-(Q12-C)") (class "Default")
      (node (ref "C5") (pin "2") (pinfunction "2_2") (pintype "passive"))
      (node (ref "Q12") (pin "3") (pinfunction "C_3") (pintype "passive"))
      (node (ref "R25") (pin "1") (pinfunction "1_1") (pintype "passive"))
    )
    (net (code "49") (name "Net-(Q13-B)") (class "Default")
      (node (ref "D34") (pin "A") (pinfunction "A_A") (pintype "passive"))
      (node (ref "Q13") (pin "2") (pinfunction "B_2") (pintype "passive"))
      (node (ref "R23") (pin "1") (pinfunction "1_1") (pintype "passive"))
    )
    (net (code "50") (name "Net-(Q13-C)") (class "Default")
      (node (ref "D36") (pin "C") (pinfunction "C_C") (pintype "passive"))
      (node (ref "Q13") (pin "3") (pinfunction "C_3") (pintype "passive"))
      (node (ref "U$2") (pin "AR2") (pinfunction "1_AR2") (pintype "bidirectional"))
    )
    (net (code "51") (name "Net-(Q14-B)") (class "Default")
      (node (ref "D37") (pin "C") (pinfunction "C_C") (pintype "passive"))
      (node (ref "D38") (pin "C") (pinfunction "C_C") (pintype "passive"))
      (node (ref "D39") (pin "C") (pinfunction "C_C") (pintype "passive"))
      (node (ref "Q14") (pin "2") (pinfunction "B_2") (pintype "passive"))
      (node (ref "R26") (pin "2") (pinfunction "2_2") (pintype "passive"))
    )
    (net (code "52") (name "Net-(Q14-C)") (class "Default")
      (node (ref "Q14") (pin "3") (pinfunction "C_3") (pintype "passive"))
      (node (ref "R27") (pin "2") (pinfunction "2_2") (pintype "passive"))
    )
    (net (code "53") (name "Net-(Q14-E)") (class "Default")
      (node (ref "D42") (pin "C") (pinfunction "C_C") (pintype "passive"))
      (node (ref "Q14") (pin "1") (pinfunction "E_1") (pintype "passive"))
    )
    (net (code "54") (name "Net-(Q15-B)") (class "Default")
      (node (ref "C6") (pin "1") (pinfunction "1_1") (pintype "passive"))
      (node (ref "D41") (pin "C") (pinfunction "C_C") (pintype "passive"))
      (node (ref "Q15") (pin "2") (pinfunction "B_2") (pintype "passive"))
      (node (ref "R29") (pin "1") (pinfunction "1_1") (pintype "passive"))
    )
    (net (code "55") (name "Net-(Q15-C)") (class "Default")
      (node (ref "C6") (pin "2") (pinfunction "2_2") (pintype "passive"))
      (node (ref "Q15") (pin "3") (pinfunction "C_3") (pintype "passive"))
      (node (ref "R30") (pin "1") (pinfunction "1_1") (pintype "passive"))
    )
    (net (code "56") (name "Net-(Q16-B)") (class "Default")
      (node (ref "D43") (pin "A") (pinfunction "A_A") (pintype "passive"))
      (node (ref "Q16") (pin "2") (pinfunction "B_2") (pintype "passive"))
      (node (ref "R28") (pin "1") (pinfunction "1_1") (pintype "passive"))
    )
    (net (code "57") (name "Net-(Q16-C)") (class "Default")
      (node (ref "D45") (pin "C") (pinfunction "C_C") (pintype "passive"))
      (node (ref "Q16") (pin "3") (pinfunction "C_3") (pintype "passive"))
      (node (ref "U$2") (pin "AU2") (pinfunction "1_AU2") (pintype "bidirectional"))
    )
    (net (code "58") (name "Net-(Q17-B)") (class "Default")
      (node (ref "D46") (pin "C") (pinfunction "C_C") (pintype "passive"))
      (node (ref "D47") (pin "C") (pinfunction "C_C") (pintype "passive"))
      (node (ref "D48") (pin "C") (pinfunction "C_C") (pintype "passive"))
      (node (ref "Q17") (pin "2") (pinfunction "B_2") (pintype "passive"))
      (node (ref "R31") (pin "2") (pinfunction "2_2") (pintype "passive"))
    )
    (net (code "59") (name "Net-(Q17-C)") (class "Default")
      (node (ref "Q17") (pin "3") (pinfunction "C_3") (pintype "passive"))
      (node (ref "R32") (pin "2") (pinfunction "2_2") (pintype "passive"))
    )
    (net (code "60") (name "Net-(Q17-E)") (class "Default")
      (node (ref "D51") (pin "C") (pinfunction "C_C") (pintype "passive"))
      (node (ref "Q17") (pin "1") (pinfunction "E_1") (pintype "passive"))
    )
    (net (code "61") (name "Net-(Q18-B)") (class "Default")
      (node (ref "C7") (pin "1") (pinfunction "1_1") (pintype "passive"))
      (node (ref "D50") (pin "C") (pinfunction "C_C") (pintype "passive"))
      (node (ref "Q18") (pin "2") (pinfunction "B_2") (pintype "passive"))
      (node (ref "R34") (pin "1") (pinfunction "1_1") (pintype "passive"))
    )
    (net (code "62") (name "Net-(Q18-C)") (class "Default")
      (node (ref "C7") (pin "2") (pinfunction "2_2") (pintype "passive"))
      (node (ref "Q18") (pin "3") (pinfunction "C_3") (pintype "passive"))
      (node (ref "R35") (pin "1") (pinfunction "1_1") (pintype "passive"))
    )
    (net (code "63") (name "Net-(Q19-B)") (class "Default")
      (node (ref "D52") (pin "A") (pinfunction "A_A") (pintype "passive"))
      (node (ref "Q19") (pin "2") (pinfunction "B_2") (pintype "passive"))
      (node (ref "R33") (pin "1") (pinfunction "1_1") (pintype "passive"))
    )
    (net (code "64") (name "Net-(Q19-C)") (class "Default")
      (node (ref "D54") (pin "C") (pinfunction "C_C") (pintype "passive"))
      (node (ref "Q19") (pin "3") (pinfunction "C_3") (pintype "passive"))
      (node (ref "U$2") (pin "BE2") (pinfunction "1_BE2") (pintype "bidirectional"))
    )
    (net (code "65") (name "Net-(Q20-B)") (class "Default")
      (node (ref "D55") (pin "C") (pinfunction "C_C") (pintype "passive"))
      (node (ref "D56") (pin "C") (pinfunction "C_C") (pintype "passive"))
      (node (ref "D57") (pin "C") (pinfunction "C_C") (pintype "passive"))
      (node (ref "Q20") (pin "2") (pinfunction "B_2") (pintype "passive"))
      (node (ref "R36") (pin "2") (pinfunction "2_2") (pintype "passive"))
    )
    (net (code "66") (name "Net-(Q20-C)") (class "Default")
      (node (ref "Q20") (pin "3") (pinfunction "C_3") (pintype "passive"))
      (node (ref "R37") (pin "2") (pinfunction "2_2") (pintype "passive"))
    )
    (net (code "67") (name "Net-(Q20-E)") (class "Default")
      (node (ref "D60") (pin "C") (pinfunction "C_C") (pintype "passive"))
      (node (ref "Q20") (pin "1") (pinfunction "E_1") (pintype "passive"))
    )
    (net (code "68") (name "Net-(Q21-B)") (class "Default")
      (node (ref "C8") (pin "1") (pinfunction "1_1") (pintype "passive"))
      (node (ref "D59") (pin "C") (pinfunction "C_C") (pintype "passive"))
      (node (ref "Q21") (pin "2") (pinfunction "B_2") (pintype "passive"))
      (node (ref "R39") (pin "1") (pinfunction "1_1") (pintype "passive"))
    )
    (net (code "69") (name "Net-(Q21-C)") (class "Default")
      (node (ref "C8") (pin "2") (pinfunction "2_2") (pintype "passive"))
      (node (ref "Q21") (pin "3") (pinfunction "C_3") (pintype "passive"))
      (node (ref "R40") (pin "1") (pinfunction "1_1") (pintype "passive"))
    )
    (net (code "70") (name "Net-(Q22-B)") (class "Default")
      (node (ref "D61") (pin "A") (pinfunction "A_A") (pintype "passive"))
      (node (ref "Q22") (pin "2") (pinfunction "B_2") (pintype "passive"))
      (node (ref "R38") (pin "1") (pinfunction "1_1") (pintype "passive"))
    )
    (net (code "71") (name "Net-(Q22-C)") (class "Default")
      (node (ref "D63") (pin "C") (pinfunction "C_C") (pintype "passive"))
      (node (ref "Q22") (pin "3") (pinfunction "C_3") (pintype "passive"))
      (node (ref "U$2") (pin "BJ2") (pinfunction "1_BJ2") (pintype "bidirectional"))
    )
    (net (code "72") (name "Net-(Q23-B)") (class "Default")
      (node (ref "D64") (pin "C") (pinfunction "C_C") (pintype "passive"))
      (node (ref "D65") (pin "C") (pinfunction "C_C") (pintype "passive"))
      (node (ref "D66") (pin "C") (pinfunction "C_C") (pintype "passive"))
      (node (ref "Q23") (pin "2") (pinfunction "B_2") (pintype "passive"))
      (node (ref "R41") (pin "2") (pinfunction "2_2") (pintype "passive"))
    )
    (net (code "73") (name "Net-(Q23-C)") (class "Default")
      (node (ref "Q23") (pin "3") (pinfunction "C_3") (pintype "passive"))
      (node (ref "R42") (pin "2") (pinfunction "2_2") (pintype "passive"))
    )
    (net (code "74") (name "Net-(Q23-E)") (class "Default")
      (node (ref "D69") (pin "C") (pinfunction "C_C") (pintype "passive"))
      (node (ref "Q23") (pin "1") (pinfunction "E_1") (pintype "passive"))
    )
    (net (code "75") (name "Net-(Q24-B)") (class "Default")
      (node (ref "C9") (pin "1") (pinfunction "1_1") (pintype "passive"))
      (node (ref "D68") (pin "C") (pinfunction "C_C") (pintype "passive"))
      (node (ref "Q24") (pin "2") (pinfunction "B_2") (pintype "passive"))
      (node (ref "R44") (pin "1") (pinfunction "1_1") (pintype "passive"))
    )
    (net (code "76") (name "Net-(Q24-C)") (class "Default")
      (node (ref "C9") (pin "2") (pinfunction "2_2") (pintype "passive"))
      (node (ref "Q24") (pin "3") (pinfunction "C_3") (pintype "passive"))
      (node (ref "R45") (pin "1") (pinfunction "1_1") (pintype "passive"))
    )
    (net (code "77") (name "Net-(Q25-B)") (class "Default")
      (node (ref "D70") (pin "A") (pinfunction "A_A") (pintype "passive"))
      (node (ref "Q25") (pin "2") (pinfunction "B_2") (pintype "passive"))
      (node (ref "R43") (pin "1") (pinfunction "1_1") (pintype "passive"))
    )
    (net (code "78") (name "Net-(Q25-C)") (class "Default")
      (node (ref "D72") (pin "C") (pinfunction "C_C") (pintype "passive"))
      (node (ref "Q25") (pin "3") (pinfunction "C_3") (pintype "passive"))
      (node (ref "U$2") (pin "BM2") (pinfunction "1_BM2") (pintype "bidirectional"))
    )
    (net (code "79") (name "Net-(R12-Pad1)") (class "Default")
      (node (ref "R12") (pin "1") (pinfunction "1_1") (pintype "passive"))
      (node (ref "R14") (pin "2") (pinfunction "2_2") (pintype "passive"))
    )
    (net (code "80") (name "Net-(R14-Pad1)") (class "Default")
      (node (ref "R14") (pin "1") (pinfunction "1_1") (pintype "passive"))
      (node (ref "R16") (pin "2") (pinfunction "2_2") (pintype "passive"))
    )
    (net (code "81") (name "Net-(R16-Pad1)") (class "Default")
      (node (ref "R16") (pin "1") (pinfunction "1_1") (pintype "passive"))
      (node (ref "R20") (pin "2") (pinfunction "2_2") (pintype "passive"))
    )
    (net (code "82") (name "Net-(U$2AD-1)") (class "Default")
      (node (ref "R25") (pin "2") (pinfunction "2_2") (pintype "passive"))
      (node (ref "U$2") (pin "AS2") (pinfunction "1_AS2") (pintype "bidirectional"))
    )
    (net (code "83") (name "Net-(U$2AF-1)") (class "Default")
      (node (ref "D37") (pin "A") (pinfunction "A_A") (pintype "passive"))
      (node (ref "U$2") (pin "AT2") (pinfunction "1_AT2") (pintype "bidirectional"))
    )
    (net (code "84") (name "Net-(U$2AJ-1)") (class "Default")
      (node (ref "R30") (pin "2") (pinfunction "2_2") (pintype "passive"))
      (node (ref "U$2") (pin "AV2") (pinfunction "1_AV2") (pintype "bidirectional"))
    )
    (net (code "85") (name "Net-(U$2AR-1)") (class "Default")
      (node (ref "D46") (pin "A") (pinfunction "A_A") (pintype "passive"))
      (node (ref "U$2") (pin "BD2") (pinfunction "1_BD2") (pintype "bidirectional"))
    )
    (net (code "86") (name "Net-(U$2AV-1)") (class "Default")
      (node (ref "R35") (pin "2") (pinfunction "2_2") (pintype "passive"))
      (node (ref "U$2") (pin "BF2") (pinfunction "1_BF2") (pintype "bidirectional"))
    )
    (net (code "87") (name "Net-(U$2AX-1)") (class "Default")
      (node (ref "D55") (pin "A") (pinfunction "A_A") (pintype "passive"))
      (node (ref "U$2") (pin "BH2") (pinfunction "1_BH2") (pintype "bidirectional"))
    )
    (net (code "88") (name "Net-(U$2BB-1)") (class "Default")
      (node (ref "R40") (pin "2") (pinfunction "2_2") (pintype "passive"))
      (node (ref "U$2") (pin "BK2") (pinfunction "1_BK2") (pintype "bidirectional"))
    )
    (net (code "89") (name "Net-(U$2BD-1)") (class "Default")
      (node (ref "D64") (pin "A") (pinfunction "A_A") (pintype "passive"))
      (node (ref "U$2") (pin "BL2") (pinfunction "1_BL2") (pintype "bidirectional"))
    )
    (net (code "90") (name "Net-(U$2BH-1)") (class "Default")
      (node (ref "R45") (pin "2") (pinfunction "2_2") (pintype "passive"))
      (node (ref "U$2") (pin "BN2") (pinfunction "1_BN2") (pintype "bidirectional"))
    )
    (net (code "91") (name "Net-(U$2BJ-1)") (class "Default")
      (node (ref "D21") (pin "A") (pinfunction "A_A") (pintype "passive"))
      (node (ref "D3") (pin "A") (pinfunction "A_A") (pintype "passive"))
      (node (ref "D39") (pin "A") (pinfunction "A_A") (pintype "passive"))
      (node (ref "D57") (pin "A") (pinfunction "A_A") (pintype "passive"))
      (node (ref "U$2") (pin "BP2") (pinfunction "1_BP2") (pintype "bidirectional"))
    )
    (net (code "92") (name "Net-(U$2BL-1)") (class "Default")
      (node (ref "D12") (pin "A") (pinfunction "A_A") (pintype "passive"))
      (node (ref "D30") (pin "A") (pinfunction "A_A") (pintype "passive"))
      (node (ref "D48") (pin "A") (pinfunction "A_A") (pintype "passive"))
      (node (ref "D66") (pin "A") (pinfunction "A_A") (pintype "passive"))
      (node (ref "U$2") (pin "BR2") (pinfunction "1_BR2") (pintype "bidirectional"))
    )
    (net (code "93") (name "Net-(U$2BN-1)") (class "Default")
      (node (ref "D11") (pin "A") (pinfunction "A_A") (pintype "passive"))
      (node (ref "D2") (pin "A") (pinfunction "A_A") (pintype "passive"))
      (node (ref "D38") (pin "A") (pinfunction "A_A") (pintype "passive"))
      (node (ref "D47") (pin "A") (pinfunction "A_A") (pintype "passive"))
      (node (ref "U$2") (pin "BS2") (pinfunction "1_BS2") (pintype "bidirectional"))
    )
    (net (code "94") (name "Net-(U$2BP-1)") (class "Default")
      (node (ref "D20") (pin "A") (pinfunction "A_A") (pintype "passive"))
      (node (ref "D29") (pin "A") (pinfunction "A_A") (pintype "passive"))
      (node (ref "D56") (pin "A") (pinfunction "A_A") (pintype "passive"))
      (node (ref "D65") (pin "A") (pinfunction "A_A") (pintype "passive"))
      (node (ref "U$2") (pin "BT2") (pinfunction "1_BT2") (pintype "bidirectional"))
    )
    (net (code "95") (name "Net-(U$2BR-1)") (class "Default")
      (node (ref "D16") (pin "A") (pinfunction "A_A") (pintype "passive"))
      (node (ref "D26") (pin "A") (pinfunction "A_A") (pintype "passive"))
      (node (ref "D35") (pin "A") (pinfunction "A_A") (pintype "passive"))
      (node (ref "D44") (pin "A") (pinfunction "A_A") (pintype "passive"))
      (node (ref "D53") (pin "A") (pinfunction "A_A") (pintype "passive"))
      (node (ref "D6") (pin "A") (pinfunction "A_A") (pintype "passive"))
      (node (ref "D62") (pin "A") (pinfunction "A_A") (pintype "passive"))
      (node (ref "D71") (pin "A") (pinfunction "A_A") (pintype "passive"))
      (node (ref "U$2") (pin "BU2") (pinfunction "1_BU2") (pintype "bidirectional"))
    )
    (net (code "96") (name "Net-(U$2BT-1)") (class "Default")
      (node (ref "R20") (pin "1") (pinfunction "1_1") (pintype "passive"))
      (node (ref "U$2") (pin "BV2") (pinfunction "1_BV2") (pintype "bidirectional"))
    )
    (net (code "97") (name "Net-(U$2H-1)") (class "Default")
      (node (ref "D1") (pin "A") (pinfunction "A_A") (pintype "passive"))
      (node (ref "U$2") (pin "AD2") (pinfunction "1_AD2") (pintype "bidirectional"))
    )
    (net (code "98") (name "Net-(U$2L-1)") (class "Default")
      (node (ref "R5") (pin "2") (pinfunction "2_2") (pintype "passive"))
      (node (ref "U$2") (pin "AF2") (pinfunction "1_AF2") (pintype "bidirectional"))
    )
    (net (code "99") (name "Net-(U$2N-1)") (class "Default")
      (node (ref "D10") (pin "A") (pinfunction "A_A") (pintype "passive"))
      (node (ref "U$2") (pin "AH2") (pinfunction "1_AH2") (pintype "bidirectional"))
    )
    (net (code "100") (name "Net-(U$2R-1)") (class "Default")
      (node (ref "R10") (pin "2") (pinfunction "2_2") (pintype "passive"))
      (node (ref "U$2") (pin "AK2") (pinfunction "1_AK2") (pintype "bidirectional"))
    )
    (net (code "101") (name "Net-(U$2T-1)") (class "Default")
      (node (ref "D19") (pin "A") (pinfunction "A_A") (pintype "passive"))
      (node (ref "U$2") (pin "AL2") (pinfunction "1_AL2") (pintype "bidirectional"))
    )
    (net (code "102") (name "Net-(U$2X-1)") (class "Default")
      (node (ref "R19") (pin "2") (pinfunction "2_2") (pintype "passive"))
      (node (ref "U$2") (pin "AN2") (pinfunction "1_AN2") (pintype "bidirectional"))
    )
    (net (code "103") (name "Net-(U$2Z-1)") (class "Default")
      (node (ref "D28") (pin "A") (pinfunction "A_A") (pintype "passive"))
      (node (ref "U$2") (pin "AP2") (pinfunction "1_AP2") (pintype "bidirectional"))
    )
  )
)
